# ReboostV2_Phase.net
KiCad netlist of a schematic drawn in Altium Designer
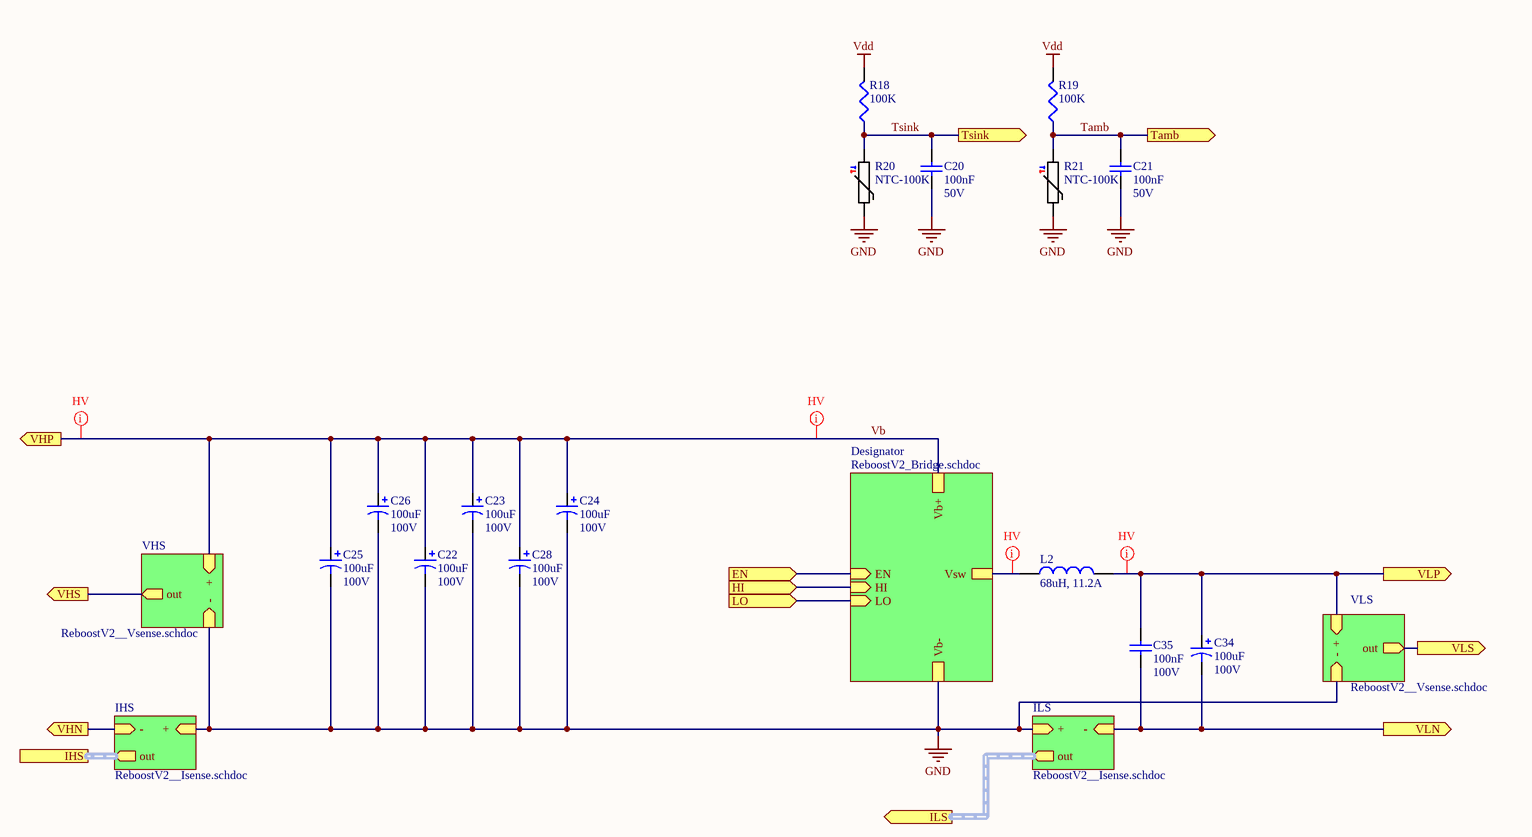
[diagram p0: ReboostV2_Phase.SchDoc]

(export (version "E")
  (design (tool "Eeschema 10.0.6"))
  (components
    (comp (ref "C20")
      (value "100nF")
      (footprint "C0603")
      (description "Capacitor, 100nF, 50V, X7R")
      (fields
        (field (name "VOLTAGE RATING") "50V")
        (field (name "MANUFACTURER") "MULTICOMP")
        (field (name "MANUFACTURER PART NUMBER") "MCCA000255")
      )
      (libsource (lib "Reboostv2") (part "100nF/0603/CER/50V"))
    )
    (comp (ref "C21")
      (value "100nF")
      (footprint "C0603")
      (description "Capacitor, 100nF, 50V, X7R")
      (fields
        (field (name "VOLTAGE RATING") "50V")
        (field (name "MANUFACTURER") "MULTICOMP")
        (field (name "MANUFACTURER PART NUMBER") "MCCA000255")
      )
      (libsource (lib "Reboostv2") (part "100nF/0603/CER/50V"))
    )
    (comp (ref "C22")
      (value "100uF")
      (footprint "WCAP-ATUL_10x20x5x0.6")
      (description "Aluminum Electrolytic Capacitor, 100uF, 100V")
      (fields
        (field (name "VOLTAGE RATING") "100V")
        (field (name "MANUFACTURER") "United Chemi-Con")
        (field (name "MANUFACTURER PART NUMBER") "EKYB101ELL101MJ20S")
      )
      (libsource (lib "Reboostv2") (part "100uF/ALU/100V"))
    )
    (comp (ref "C23")
      (value "100uF")
      (footprint "WCAP-ATUL_10x20x5x0.6")
      (description "Aluminum Electrolytic Capacitor, 100uF, 100V")
      (fields
        (field (name "VOLTAGE RATING") "100V")
        (field (name "MANUFACTURER") "United Chemi-Con")
        (field (name "MANUFACTURER PART NUMBER") "EKYB101ELL101MJ20S")
      )
      (libsource (lib "Reboostv2") (part "100uF/ALU/100V"))
    )
    (comp (ref "C24")
      (value "100uF")
      (footprint "WCAP-ATUL_10x20x5x0.6")
      (description "Aluminum Electrolytic Capacitor, 100uF, 100V")
      (fields
        (field (name "VOLTAGE RATING") "100V")
        (field (name "MANUFACTURER") "United Chemi-Con")
        (field (name "MANUFACTURER PART NUMBER") "EKYB101ELL101MJ20S")
      )
      (libsource (lib "Reboostv2") (part "100uF/ALU/100V"))
    )
    (comp (ref "C25")
      (value "100uF")
      (footprint "WCAP-ATUL_10x20x5x0.6")
      (description "Aluminum Electrolytic Capacitor, 100uF, 100V")
      (fields
        (field (name "VOLTAGE RATING") "100V")
        (field (name "MANUFACTURER") "United Chemi-Con")
        (field (name "MANUFACTURER PART NUMBER") "EKYB101ELL101MJ20S")
      )
      (libsource (lib "Reboostv2") (part "100uF/ALU/100V"))
    )
    (comp (ref "C26")
      (value "100uF")
      (footprint "WCAP-ATUL_10x20x5x0.6")
      (description "Aluminum Electrolytic Capacitor, 100uF, 100V")
      (fields
        (field (name "VOLTAGE RATING") "100V")
        (field (name "MANUFACTURER") "United Chemi-Con")
        (field (name "MANUFACTURER PART NUMBER") "EKYB101ELL101MJ20S")
      )
      (libsource (lib "Reboostv2") (part "100uF/ALU/100V"))
    )
    (comp (ref "C28")
      (value "100uF")
      (footprint "WCAP-ATUL_10x20x5x0.6")
      (description "Aluminum Electrolytic Capacitor, 100uF, 100V")
      (fields
        (field (name "VOLTAGE RATING") "100V")
        (field (name "MANUFACTURER") "United Chemi-Con")
        (field (name "MANUFACTURER PART NUMBER") "EKYB101ELL101MJ20S")
      )
      (libsource (lib "Reboostv2") (part "100uF/ALU/100V"))
    )
    (comp (ref "C34")
      (value "100uF")
      (footprint "WCAP-ATUL_10x20x5x0.6")
      (description "Aluminum Electrolytic Capacitor, 100uF, 100V")
      (fields
        (field (name "VOLTAGE RATING") "100V")
        (field (name "MANUFACTURER") "United Chemi-Con")
        (field (name "MANUFACTURER PART NUMBER") "EKYB101ELL101MJ20S")
      )
      (libsource (lib "Reboostv2") (part "100uF/ALU/100V"))
    )
    (comp (ref "C35")
      (value "100nF")
      (footprint "C-0805")
      (description "Capacitor, 100nF, 100V, X7R")
      (fields
        (field (name "VOLTAGE RATING") "100V")
        (field (name "MANUFACTURER") "KEMET")
        (field (name "MANUFACTURER PART NUMBER") "C0805C104K1RACTU")
      )
      (libsource (lib "Reboostv2") (part "100nF/0805/CER/100V"))
    )
    (comp (ref "L2")
      (value "68uH, 11.2A")
      (footprint "WE-HCF_2920")
      (description "WE-HCF SMT High Current Inductor, size 2920, 68uH, 11.2A, 24.42mOhm")
      (fields
        (field (name "MANUFACTURER") "Wurth Elektronik")
        (field (name "MANUFACTURER PART NUMBER") "74437429203680")
      )
      (libsource (lib "Reboostv2") (part "74437429203680"))
    )
    (comp (ref "R18")
      (value "100K")
      (footprint "0603")
      (description "Resistor, 100K, 1%, 0.063W, 50V, 100PPM, 0603")
      (fields
        (field (name "MANUFACTURER") "VISHAY DRALORIC")
        (field (name "MANUFACTURER PART NUMBER") "CRCW0603100KFKEA")
      )
      (libsource (lib "Reboostv2") (part "100K/0603/0063W/50V"))
    )
    (comp (ref "R19")
      (value "100K")
      (footprint "0603")
      (description "Resistor, 100K, 1%, 0.063W, 50V, 100PPM, 0603")
      (fields
        (field (name "MANUFACTURER") "VISHAY DRALORIC")
        (field (name "MANUFACTURER PART NUMBER") "CRCW0603100KFKEA")
      )
      (libsource (lib "Reboostv2") (part "100K/0603/0063W/50V"))
    )
    (comp (ref "R20")
      (value "NTC-100K")
      (footprint "R0805")
      (description "NTC, 100K, 25°C, 0.5%, 0.210W, 0805")
      (fields (field (name "MANUFACTURER") "VISHAY BC COMPONENTS") (field (name "MPN") "NTCS0805E4104JMT"))
      (libsource (lib "Reboostv2") (part "NTCS0805E4104JMT"))
    )
    (comp (ref "R21")
      (value "NTC-100K")
      (footprint "R0805")
      (description "NTC, 100K, 25°C, 0.5%, 0.210W, 0805")
      (fields (field (name "MANUFACTURER") "VISHAY BC COMPONENTS") (field (name "MPN") "NTCS0805E4104JMT"))
      (libsource (lib "Reboostv2") (part "NTCS0805E4104JMT"))
    )
  )
  (nets
    (net (code "6") (name "/Tamb") (class "Default")
      (node (ref "C21") (pin "2") (pinfunction "2_2") (pintype "passive"))
      (node (ref "R19") (pin "1") (pinfunction "1_1") (pintype "passive"))
      (node (ref "R21") (pin "2") (pinfunction "2_2") (pintype "passive"))
    )
    (net (code "7") (name "/Tsink") (class "Default")
      (node (ref "C20") (pin "2") (pinfunction "2_2") (pintype "passive"))
      (node (ref "R18") (pin "1") (pinfunction "1_1") (pintype "passive"))
      (node (ref "R20") (pin "2") (pinfunction "2_2") (pintype "passive"))
    )
    (net (code "10") (name "/VLN") (class "Default")
      (node (ref "C34") (pin "2") (pinfunction "2_2") (pintype "passive"))
      (node (ref "C35") (pin "1") (pinfunction "1_1") (pintype "passive"))
    )
    (net (code "11") (name "/VLP") (class "Default")
      (node (ref "C34") (pin "1") (pinfunction "1_1") (pintype "passive"))
      (node (ref "C35") (pin "2") (pinfunction "2_2") (pintype "passive"))
      (node (ref "L2") (pin "2") (pinfunction "2_2") (pintype "passive"))
    )
    (net (code "13") (name "/Vb") (class "Default")
      (node (ref "C22") (pin "1") (pinfunction "1_1") (pintype "passive"))
      (node (ref "C23") (pin "1") (pinfunction "1_1") (pintype "passive"))
      (node (ref "C24") (pin "1") (pinfunction "1_1") (pintype "passive"))
      (node (ref "C25") (pin "1") (pinfunction "1_1") (pintype "passive"))
      (node (ref "C26") (pin "1") (pinfunction "1_1") (pintype "passive"))
      (node (ref "C28") (pin "1") (pinfunction "1_1") (pintype "passive"))
    )
    (net (code "14") (name "/Vsw") (class "Default")
      (node (ref "L2") (pin "1") (pinfunction "1_1") (pintype "passive"))
    )
    (net (code "15") (name "GND") (class "Default")
      (node (ref "C20") (pin "1") (pinfunction "1_1") (pintype "passive"))
      (node (ref "C21") (pin "1") (pinfunction "1_1") (pintype "passive"))
      (node (ref "C22") (pin "2") (pinfunction "2_2") (pintype "passive"))
      (node (ref "C23") (pin "2") (pinfunction "2_2") (pintype "passive"))
      (node (ref "C24") (pin "2") (pinfunction "2_2") (pintype "passive"))
      (node (ref "C25") (pin "2") (pinfunction "2_2") (pintype "passive"))
      (node (ref "C26") (pin "2") (pinfunction "2_2") (pintype "passive"))
      (node (ref "C28") (pin "2") (pinfunction "2_2") (pintype "passive"))
      (node (ref "R20") (pin "1") (pinfunction "1_1") (pintype "passive"))
      (node (ref "R21") (pin "1") (pinfunction "1_1") (pintype "passive"))
    )
    (net (code "16") (name "Vdd") (class "Default")
      (node (ref "R18") (pin "2") (pinfunction "2_2") (pintype "passive"))
      (node (ref "R19") (pin "2") (pinfunction "2_2") (pintype "passive"))
    )
  )
)
